# 4_sensors.net
KiCad netlist of a schematic drawn in Altium Designer
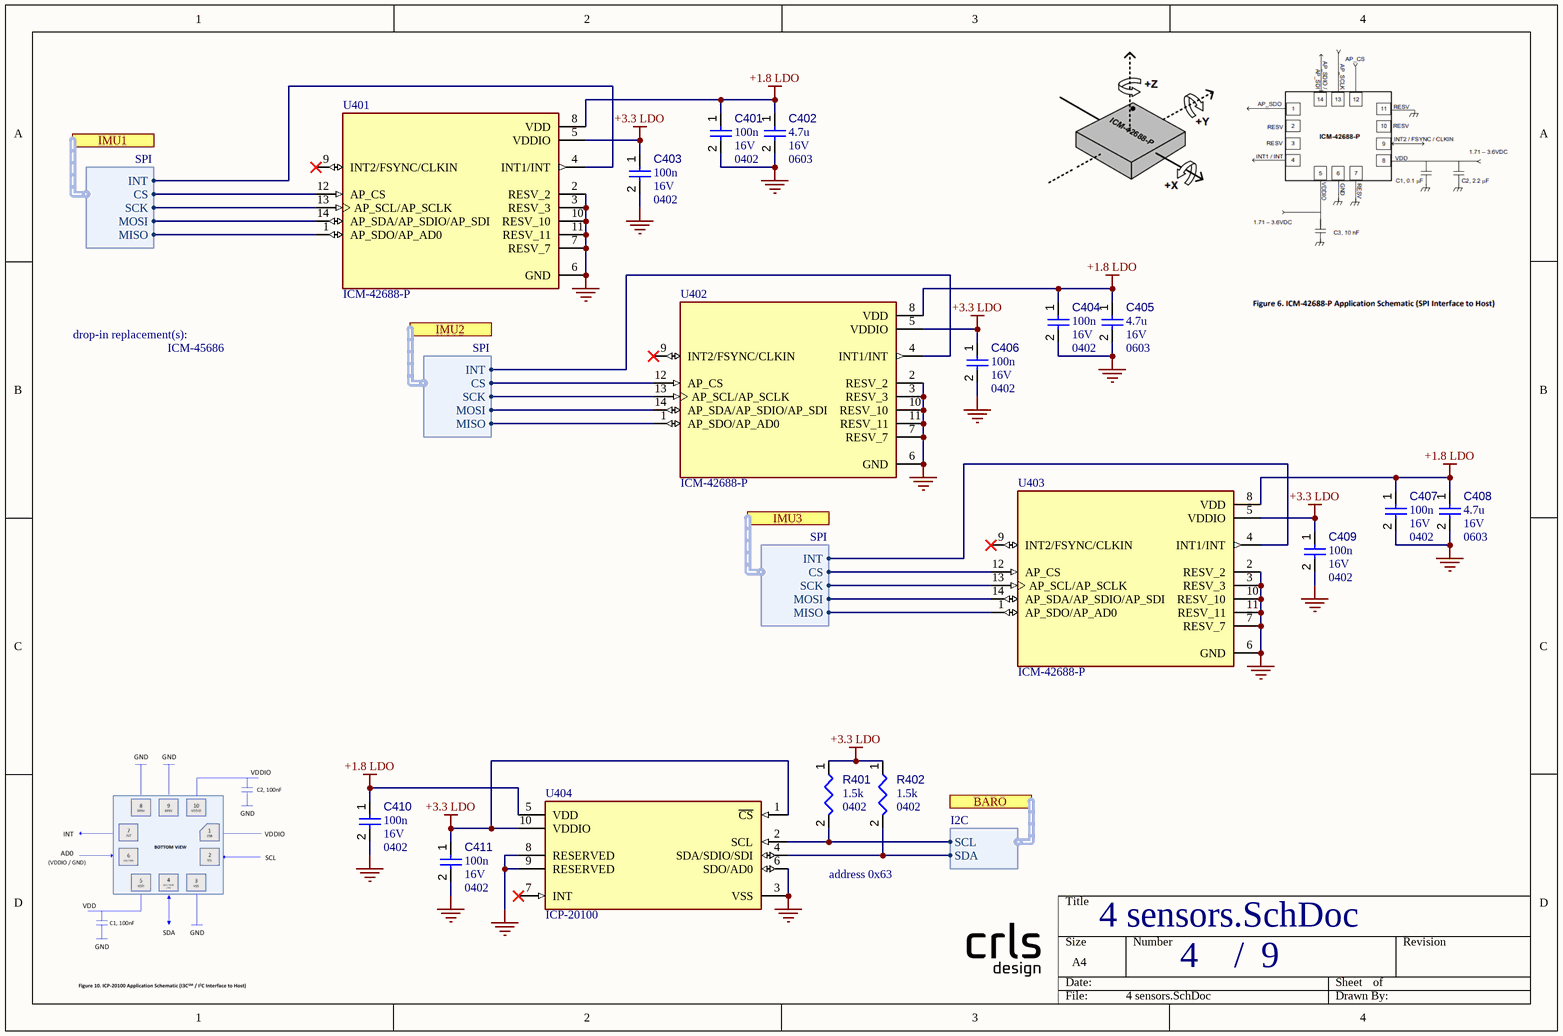
[diagram p0: 4 sensors.SchDoc]

(export (version "E")
  (design (tool "Eeschema 10.0.6"))
  (components
    (comp (ref "C401")
      (value "100n")
      (footprint "CAPC0402(1005)60_L")
      (description "Capacitor")
      (fields
        (field (name "CASE/PACKAGE") "0402")
        (field (name "VOLTAGE RATING") "16V")
        (field (name "Comment") "Capacitors,0402,100n,16V")
      )
      (libsource (lib "UBC Uncrewed Aircraft Systems") (part "CAP-NP-2"))
    )
    (comp (ref "C402")
      (value "4.7u")
      (footprint "CAPC0603(1608)100_L")
      (description "Capacitor")
      (fields
        (field (name "CASE/PACKAGE") "0603")
        (field (name "VOLTAGE RATING") "16V")
        (field (name "Comment") "Capacitors,0603,4.7u,16V")
      )
      (libsource (lib "UBC Uncrewed Aircraft Systems") (part "CAP-NP-2"))
    )
    (comp (ref "C403")
      (value "100n")
      (footprint "CAPC0402(1005)60_L")
      (description "Capacitor")
      (fields
        (field (name "CASE/PACKAGE") "0402")
        (field (name "VOLTAGE RATING") "16V")
        (field (name "Comment") "Capacitors,0402,100n,16V")
      )
      (libsource (lib "UBC Uncrewed Aircraft Systems") (part "CAP-NP-2"))
    )
    (comp (ref "C404")
      (value "100n")
      (footprint "CAPC0402(1005)60_L")
      (description "Capacitor")
      (fields
        (field (name "CASE/PACKAGE") "0402")
        (field (name "VOLTAGE RATING") "16V")
        (field (name "Comment") "Capacitors,0402,100n,16V")
      )
      (libsource (lib "UBC Uncrewed Aircraft Systems") (part "CAP-NP-2"))
    )
    (comp (ref "C405")
      (value "4.7u")
      (footprint "CAPC0603(1608)100_L")
      (description "Capacitor")
      (fields
        (field (name "CASE/PACKAGE") "0603")
        (field (name "VOLTAGE RATING") "16V")
        (field (name "Comment") "Capacitors,0603,4.7u,16V")
      )
      (libsource (lib "UBC Uncrewed Aircraft Systems") (part "CAP-NP-2"))
    )
    (comp (ref "C406")
      (value "100n")
      (footprint "CAPC0402(1005)60_L")
      (description "Capacitor")
      (fields
        (field (name "CASE/PACKAGE") "0402")
        (field (name "VOLTAGE RATING") "16V")
        (field (name "Comment") "Capacitors,0402,100n,16V")
      )
      (libsource (lib "UBC Uncrewed Aircraft Systems") (part "CAP-NP-2"))
    )
    (comp (ref "C407")
      (value "100n")
      (footprint "CAPC0402(1005)60_L")
      (description "Capacitor")
      (fields
        (field (name "CASE/PACKAGE") "0402")
        (field (name "VOLTAGE RATING") "16V")
        (field (name "Comment") "Capacitors,0402,100n,16V")
      )
      (libsource (lib "UBC Uncrewed Aircraft Systems") (part "CAP-NP-2"))
    )
    (comp (ref "C408")
      (value "4.7u")
      (footprint "CAPC0603(1608)100_L")
      (description "Capacitor")
      (fields
        (field (name "CASE/PACKAGE") "0603")
        (field (name "VOLTAGE RATING") "16V")
        (field (name "Comment") "Capacitors,0603,4.7u,16V")
      )
      (libsource (lib "UBC Uncrewed Aircraft Systems") (part "CAP-NP-2"))
    )
    (comp (ref "C409")
      (value "100n")
      (footprint "CAPC0402(1005)60_L")
      (description "Capacitor")
      (fields
        (field (name "CASE/PACKAGE") "0402")
        (field (name "VOLTAGE RATING") "16V")
        (field (name "Comment") "Capacitors,0402,100n,16V")
      )
      (libsource (lib "UBC Uncrewed Aircraft Systems") (part "CAP-NP-2"))
    )
    (comp (ref "C410")
      (value "100n")
      (footprint "CAPC0402(1005)60_L")
      (description "Capacitor")
      (fields
        (field (name "CASE/PACKAGE") "0402")
        (field (name "VOLTAGE RATING") "16V")
        (field (name "Comment") "Capacitors,0402,100n,16V")
      )
      (libsource (lib "UBC Uncrewed Aircraft Systems") (part "CAP-NP-2"))
    )
    (comp (ref "C411")
      (value "100n")
      (footprint "CAPC0402(1005)60_L")
      (description "Capacitor")
      (fields
        (field (name "CASE/PACKAGE") "0402")
        (field (name "VOLTAGE RATING") "16V")
        (field (name "Comment") "Capacitors,0402,100n,16V")
      )
      (libsource (lib "UBC Uncrewed Aircraft Systems") (part "CAP-NP-2"))
    )
    (comp (ref "R401")
      (value "1.5k")
      (footprint "RESC0402(1005)_L")
      (description "Resistor")
      (fields
        (field (name "CASE/PACKAGE") "0402")
        (field (name "TOLERANCE") "1%")
        (field (name "Comment") "Resistors,0402,1%,1.5k")
      )
      (libsource (lib "UBC Uncrewed Aircraft Systems") (part "RES-2"))
    )
    (comp (ref "R402")
      (value "1.5k")
      (footprint "RESC0402(1005)_L")
      (description "Resistor")
      (fields
        (field (name "CASE/PACKAGE") "0402")
        (field (name "TOLERANCE") "1%")
        (field (name "Comment") "Resistors,0402,1%,1.5k")
      )
      (libsource (lib "UBC Uncrewed Aircraft Systems") (part "RES-2"))
    )
    (comp (ref "U401")
      (value "ICM-42688-P")
      (footprint "PQFN50P300X250X97-14N")
      (description "Accelerometer, Gyroscope, 6 Axis Sensor Output")
      (libsource (lib "ICM-42688-P") (part "ICM-42688-P"))
    )
    (comp (ref "U402")
      (value "ICM-42688-P")
      (footprint "PQFN50P300X250X97-14N")
      (description "Accelerometer, Gyroscope, 6 Axis Sensor Output")
      (libsource (lib "ICM-42688-P") (part "ICM-42688-P"))
    )
    (comp (ref "U403")
      (value "ICM-42688-P")
      (footprint "PQFN50P300X250X97-14N")
      (description "Accelerometer, Gyroscope, 6 Axis Sensor Output")
      (libsource (lib "ICM-42688-P") (part "ICM-42688-P"))
    )
    (comp (ref "U404")
      (value "ICP-20100")
      (footprint "FP-ICP-20100-MFG")
      (description "ICP-20100 Barometric Pressure and Temperature Sensor IC Digital Output 1.8V/3.3V 10-Pin LGA T/R")
      (libsource (lib "Altium Content Vault") (part "2c5c2094cf923c2d68761797ff94764"))
    )
  )
  (nets
    (net (code "3") (name "+1.8 LDO") (class "Default")
      (node (ref "C401") (pin "1") (pinfunction "1_1") (pintype "passive"))
      (node (ref "C402") (pin "1") (pinfunction "1_1") (pintype "passive"))
      (node (ref "C404") (pin "1") (pinfunction "1_1") (pintype "passive"))
      (node (ref "C405") (pin "1") (pinfunction "1_1") (pintype "passive"))
      (node (ref "C407") (pin "1") (pinfunction "1_1") (pintype "passive"))
      (node (ref "C408") (pin "1") (pinfunction "1_1") (pintype "passive"))
      (node (ref "C410") (pin "1") (pinfunction "1_1") (pintype "passive"))
      (node (ref "U401") (pin "8") (pinfunction "VDD_8") (pintype "power_in"))
      (node (ref "U402") (pin "8") (pinfunction "VDD_8") (pintype "power_in"))
      (node (ref "U403") (pin "8") (pinfunction "VDD_8") (pintype "power_in"))
      (node (ref "U404") (pin "5") (pinfunction "VDD_5") (pintype "power_in"))
    )
    (net (code "4") (name "+3.3 LDO") (class "Default")
      (node (ref "C403") (pin "1") (pinfunction "1_1") (pintype "passive"))
      (node (ref "C406") (pin "1") (pinfunction "1_1") (pintype "passive"))
      (node (ref "C409") (pin "1") (pinfunction "1_1") (pintype "passive"))
      (node (ref "C411") (pin "1") (pinfunction "1_1") (pintype "passive"))
      (node (ref "R401") (pin "1") (pinfunction "1_1") (pintype "passive"))
      (node (ref "R402") (pin "1") (pinfunction "1_1") (pintype "passive"))
      (node (ref "U401") (pin "5") (pinfunction "VDDIO_5") (pintype "power_in"))
      (node (ref "U402") (pin "5") (pinfunction "VDDIO_5") (pintype "power_in"))
      (node (ref "U403") (pin "5") (pinfunction "VDDIO_5") (pintype "power_in"))
      (node (ref "U404") (pin "1") (pinfunction "~{CS}_1") (pintype "input"))
      (node (ref "U404") (pin "10") (pinfunction "VDDIO_10") (pintype "power_in"))
    )
    (net (code "5") (name "/SCL") (class "Default")
      (node (ref "R401") (pin "2") (pinfunction "2_2") (pintype "passive"))
      (node (ref "U404") (pin "2") (pinfunction "SCL_2") (pintype "input"))
    )
    (net (code "6") (name "/SDA") (class "Default")
      (node (ref "R402") (pin "2") (pinfunction "2_2") (pintype "passive"))
      (node (ref "U404") (pin "4") (pinfunction "SDA/SDIO/SDI_4") (pintype "bidirectional"))
    )
    (net (code "9") (name "GND") (class "Default")
      (node (ref "C401") (pin "2") (pinfunction "2_2") (pintype "passive"))
      (node (ref "C402") (pin "2") (pinfunction "2_2") (pintype "passive"))
      (node (ref "C403") (pin "2") (pinfunction "2_2") (pintype "passive"))
      (node (ref "C404") (pin "2") (pinfunction "2_2") (pintype "passive"))
      (node (ref "C405") (pin "2") (pinfunction "2_2") (pintype "passive"))
      (node (ref "C406") (pin "2") (pinfunction "2_2") (pintype "passive"))
      (node (ref "C407") (pin "2") (pinfunction "2_2") (pintype "passive"))
      (node (ref "C408") (pin "2") (pinfunction "2_2") (pintype "passive"))
      (node (ref "C409") (pin "2") (pinfunction "2_2") (pintype "passive"))
      (node (ref "C410") (pin "2") (pinfunction "2_2") (pintype "passive"))
      (node (ref "C411") (pin "2") (pinfunction "2_2") (pintype "passive"))
      (node (ref "U401") (pin "10") (pinfunction "RESV_10_10") (pintype "passive"))
      (node (ref "U401") (pin "11") (pinfunction "RESV_11_11") (pintype "passive"))
      (node (ref "U401") (pin "2") (pinfunction "RESV_2_2") (pintype "passive"))
      (node (ref "U401") (pin "3") (pinfunction "RESV_3_3") (pintype "passive"))
      (node (ref "U401") (pin "6") (pinfunction "GND_6") (pintype "power_in"))
      (node (ref "U401") (pin "7") (pinfunction "RESV_7_7") (pintype "passive"))
      (node (ref "U402") (pin "10") (pinfunction "RESV_10_10") (pintype "passive"))
      (node (ref "U402") (pin "11") (pinfunction "RESV_11_11") (pintype "passive"))
      (node (ref "U402") (pin "2") (pinfunction "RESV_2_2") (pintype "passive"))
      (node (ref "U402") (pin "3") (pinfunction "RESV_3_3") (pintype "passive"))
      (node (ref "U402") (pin "6") (pinfunction "GND_6") (pintype "power_in"))
      (node (ref "U402") (pin "7") (pinfunction "RESV_7_7") (pintype "passive"))
      (node (ref "U403") (pin "10") (pinfunction "RESV_10_10") (pintype "passive"))
      (node (ref "U403") (pin "11") (pinfunction "RESV_11_11") (pintype "passive"))
      (node (ref "U403") (pin "2") (pinfunction "RESV_2_2") (pintype "passive"))
      (node (ref "U403") (pin "3") (pinfunction "RESV_3_3") (pintype "passive"))
      (node (ref "U403") (pin "6") (pinfunction "GND_6") (pintype "power_in"))
      (node (ref "U403") (pin "7") (pinfunction "RESV_7_7") (pintype "passive"))
      (node (ref "U404") (pin "3") (pinfunction "VSS_3") (pintype "power_in"))
      (node (ref "U404") (pin "6") (pinfunction "SDO/AD0_6") (pintype "bidirectional"))
      (node (ref "U404") (pin "8") (pinfunction "RESERVED_8") (pintype "passive"))
      (node (ref "U404") (pin "9") (pinfunction "RESERVED_9") (pintype "passive"))
    )
    (net (code "10") (name "unconnected-(U401-AP_CS-Pad12)") (class "Default")
      (node (ref "U401") (pin "12") (pinfunction "AP_CS_12") (pintype "input"))
    )
    (net (code "11") (name "unconnected-(U401-AP_SCL{slash}AP_SCLK-Pad13)") (class "Default")
      (node (ref "U401") (pin "13") (pinfunction "AP_SCL/AP_SCLK_13") (pintype "input"))
    )
    (net (code "12") (name "unconnected-(U401-AP_SDA{slash}AP_SDIO{slash}AP_SDI-Pad14)") (class "Default")
      (node (ref "U401") (pin "14") (pinfunction "AP_SDA/AP_SDIO/AP_SDI_14") (pintype "bidirectional"))
    )
    (net (code "13") (name "unconnected-(U401-AP_SDO{slash}AP_AD0-Pad1)") (class "Default")
      (node (ref "U401") (pin "1") (pinfunction "AP_SDO/AP_AD0_1") (pintype "bidirectional"))
    )
    (net (code "14") (name "unconnected-(U401-INT1{slash}INT-Pad4)") (class "Default")
      (node (ref "U401") (pin "4") (pinfunction "INT1/INT_4") (pintype "output"))
    )
    (net (code "15") (name "unconnected-(U401-INT2{slash}FSYNC{slash}CLKIN-Pad9)") (class "Default")
      (node (ref "U401") (pin "9") (pinfunction "INT2/FSYNC/CLKIN_9") (pintype "bidirectional+no_connect"))
    )
    (net (code "16") (name "unconnected-(U402-AP_CS-Pad12)") (class "Default")
      (node (ref "U402") (pin "12") (pinfunction "AP_CS_12") (pintype "input"))
    )
    (net (code "17") (name "unconnected-(U402-AP_SCL{slash}AP_SCLK-Pad13)") (class "Default")
      (node (ref "U402") (pin "13") (pinfunction "AP_SCL/AP_SCLK_13") (pintype "input"))
    )
    (net (code "18") (name "unconnected-(U402-AP_SDA{slash}AP_SDIO{slash}AP_SDI-Pad14)") (class "Default")
      (node (ref "U402") (pin "14") (pinfunction "AP_SDA/AP_SDIO/AP_SDI_14") (pintype "bidirectional"))
    )
    (net (code "19") (name "unconnected-(U402-AP_SDO{slash}AP_AD0-Pad1)") (class "Default")
      (node (ref "U402") (pin "1") (pinfunction "AP_SDO/AP_AD0_1") (pintype "bidirectional"))
    )
    (net (code "20") (name "unconnected-(U402-INT1{slash}INT-Pad4)") (class "Default")
      (node (ref "U402") (pin "4") (pinfunction "INT1/INT_4") (pintype "output"))
    )
    (net (code "21") (name "unconnected-(U402-INT2{slash}FSYNC{slash}CLKIN-Pad9)") (class "Default")
      (node (ref "U402") (pin "9") (pinfunction "INT2/FSYNC/CLKIN_9") (pintype "bidirectional+no_connect"))
    )
    (net (code "22") (name "unconnected-(U403-AP_CS-Pad12)") (class "Default")
      (node (ref "U403") (pin "12") (pinfunction "AP_CS_12") (pintype "input"))
    )
    (net (code "23") (name "unconnected-(U403-AP_SCL{slash}AP_SCLK-Pad13)") (class "Default")
      (node (ref "U403") (pin "13") (pinfunction "AP_SCL/AP_SCLK_13") (pintype "input"))
    )
    (net (code "24") (name "unconnected-(U403-AP_SDA{slash}AP_SDIO{slash}AP_SDI-Pad14)") (class "Default")
      (node (ref "U403") (pin "14") (pinfunction "AP_SDA/AP_SDIO/AP_SDI_14") (pintype "bidirectional"))
    )
    (net (code "25") (name "unconnected-(U403-AP_SDO{slash}AP_AD0-Pad1)") (class "Default")
      (node (ref "U403") (pin "1") (pinfunction "AP_SDO/AP_AD0_1") (pintype "bidirectional"))
    )
    (net (code "26") (name "unconnected-(U403-INT1{slash}INT-Pad4)") (class "Default")
      (node (ref "U403") (pin "4") (pinfunction "INT1/INT_4") (pintype "output"))
    )
    (net (code "27") (name "unconnected-(U403-INT2{slash}FSYNC{slash}CLKIN-Pad9)") (class "Default")
      (node (ref "U403") (pin "9") (pinfunction "INT2/FSYNC/CLKIN_9") (pintype "bidirectional+no_connect"))
    )
    (net (code "28") (name "unconnected-(U404-INT-Pad7)") (class "Default")
      (node (ref "U404") (pin "7") (pinfunction "INT_7") (pintype "input+no_connect"))
    )
  )
)
